# Motherboard.net
KiCad netlist of a schematic drawn in Altium Designer
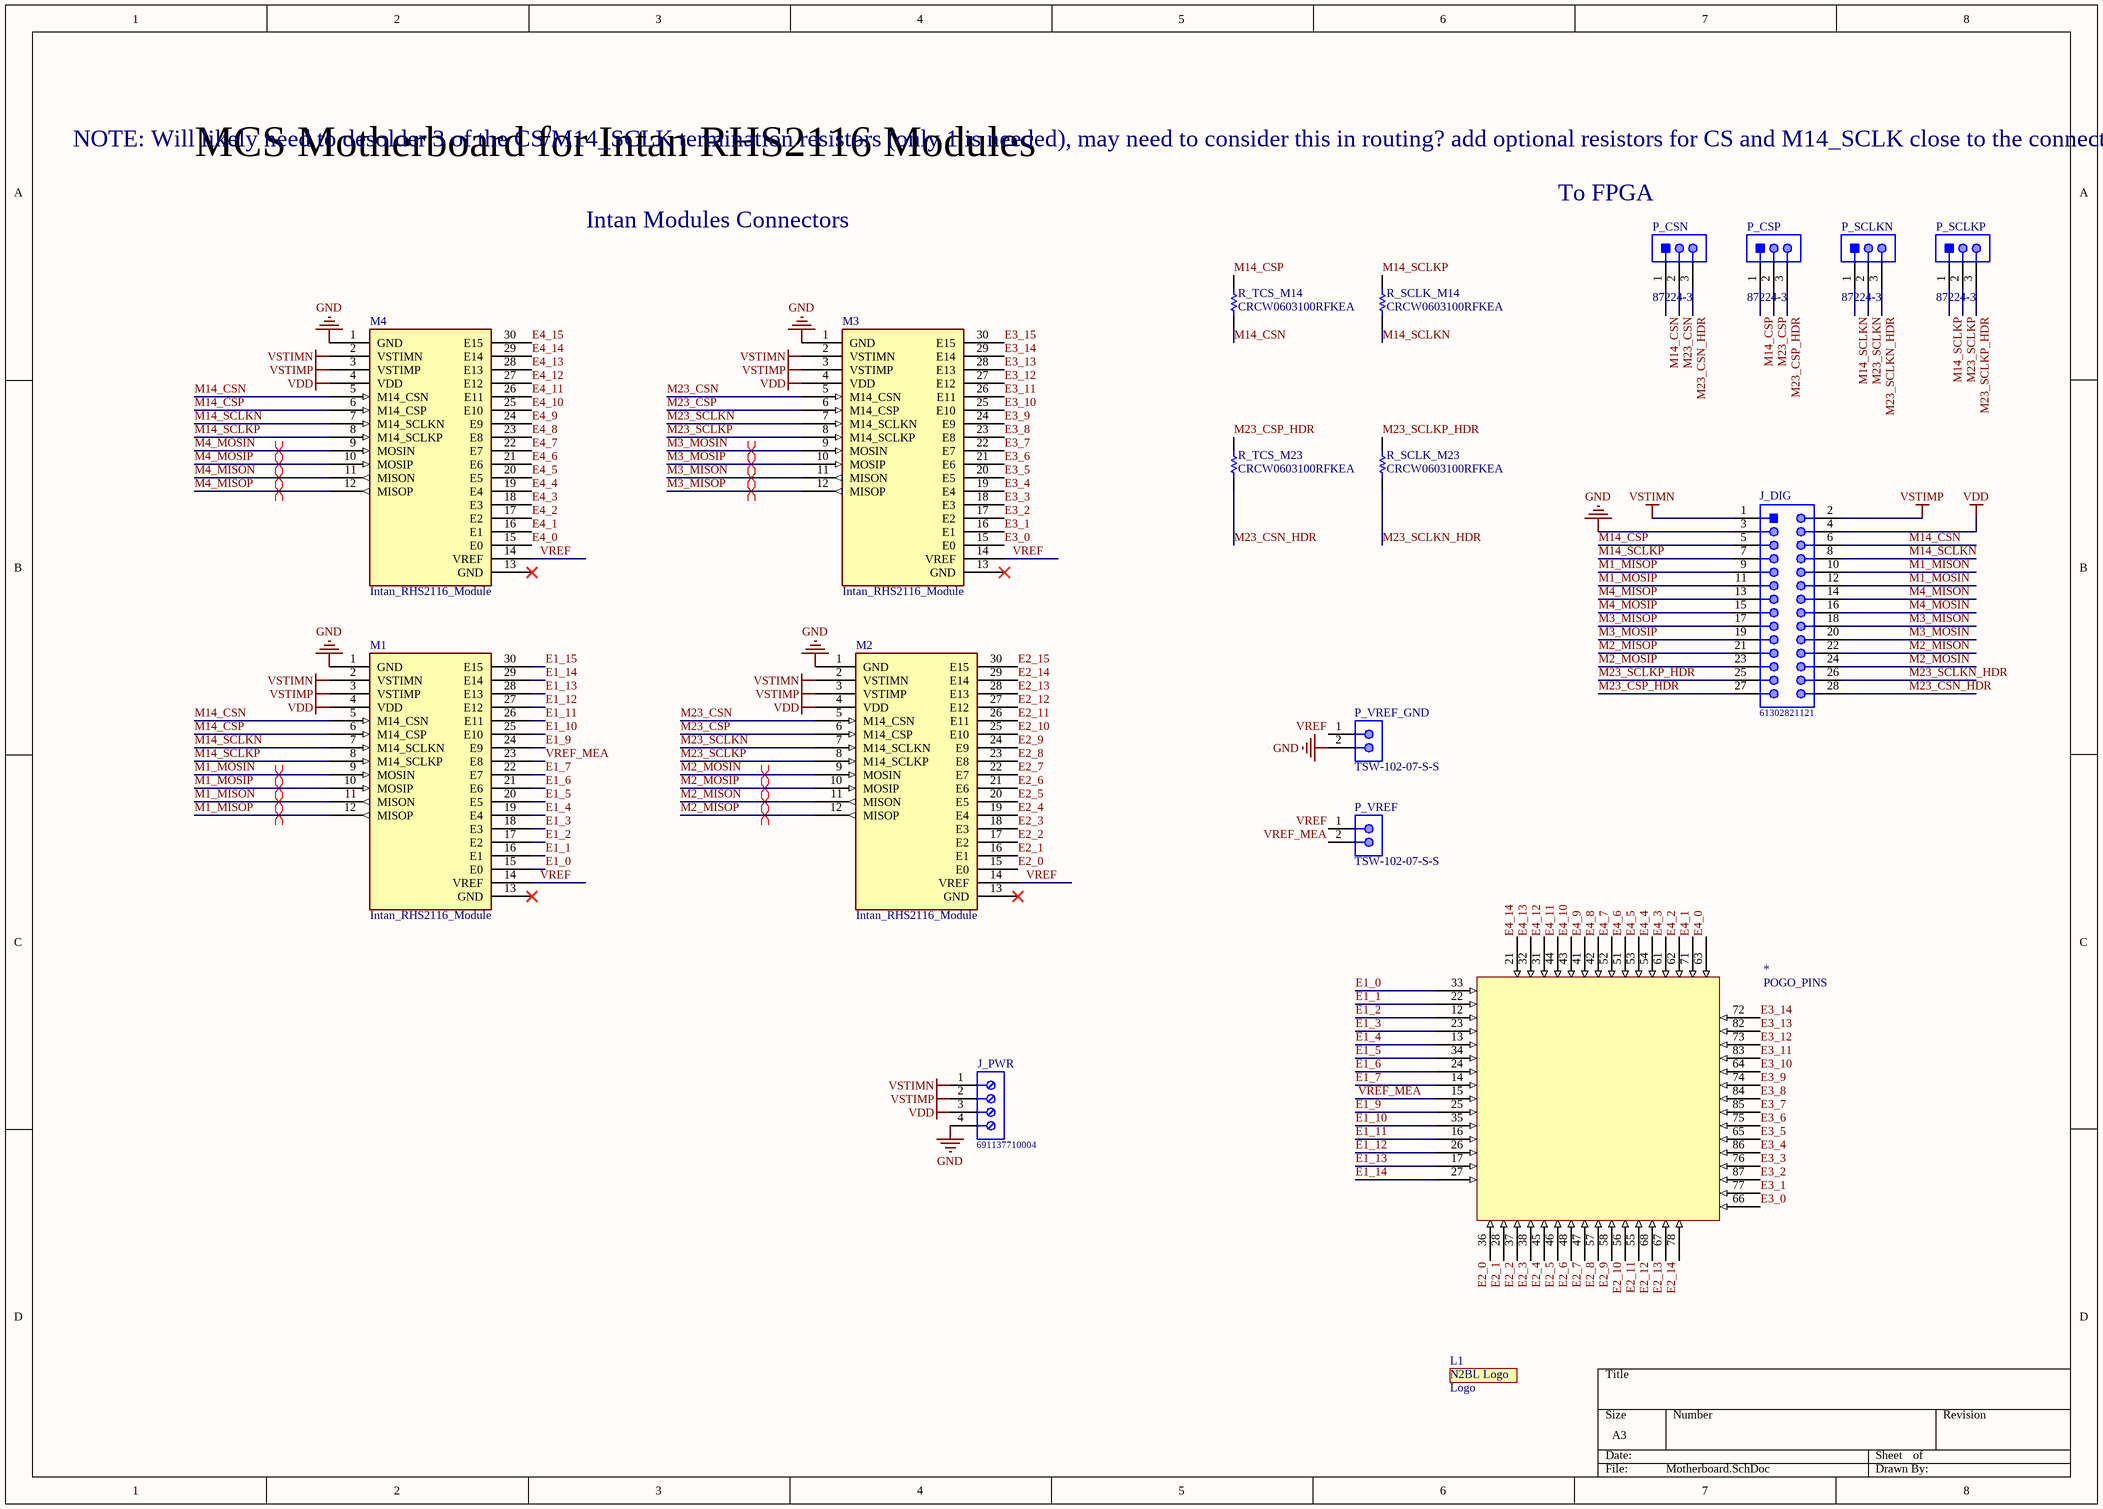
[diagram p0: Motherboard.SchDoc]

(export (version "E")
  (design (tool "Eeschema 10.0.6"))
  (components
    (comp (ref "*") (value "POGO_PINS") (footprint "POGO_PINS") (libsource (lib "V004") (part "POGO_PINS")))
    (comp (ref "J_DIG")
      (value "61302821121")
      (footprint "61302821121")
      (description "THT Vertical Pin Header WR-PHD, Pitch 2.54 mm, Dual Row, 28 pins")
      (fields (field (name "MANUFACTURER") "Wurth Elektronik") (field (name "PUBLISHER") "WurthElektronik"))
      (libsource (lib "Altium Content Vault") (part "WE-CN-2P-M-R28"))
    )
    (comp (ref "J_PWR")
      (value "691137710004")
      (footprint "691137710004")
      (description "Series 1377 - 5.00 mm Horizontal Entry with Pressure Clamp WR-TBL, 4 pin")
      (fields (field (name "MANUFACTURER") "Wurth Elektronik") (field (name "PUBLISHER") "WurthElektronik"))
      (libsource (lib "Altium Content Vault") (part "WE-CN-1P-F-TB4"))
    )
    (comp (ref "L1")
      (value "Logo")
      (footprint "N2BL_Logo")
      (libsource (lib "logo") (part "Neuron To Brain Lab Logo"))
    )
    (comp (ref "M1")
      (value "Intan_RHS2116_Module")
      (footprint "Intan_RHS2116_Module")
      (libsource (lib "V004") (part "Intan_RHS2116_Module"))
    )
    (comp (ref "M2")
      (value "Intan_RHS2116_Module")
      (footprint "Intan_RHS2116_Module")
      (libsource (lib "V004") (part "Intan_RHS2116_Module"))
    )
    (comp (ref "M3")
      (value "Intan_RHS2116_Module")
      (footprint "Intan_RHS2116_Module")
      (libsource (lib "V004") (part "Intan_RHS2116_Module"))
    )
    (comp (ref "M4")
      (value "Intan_RHS2116_Module")
      (footprint "Intan_RHS2116_Module")
      (libsource (lib "V004") (part "Intan_RHS2116_Module"))
    )
    (comp (ref "P_CSN")
      (value "87224-3")
      (footprint "TECO-87224-3_V")
      (fields (field (name "MANUFACTURER") "TE Connectivity"))
      (libsource (lib "Altium Content Vault") (part "CN-1P-M-R3"))
    )
    (comp (ref "P_CSP")
      (value "87224-3")
      (footprint "TECO-87224-3_V")
      (fields (field (name "MANUFACTURER") "TE Connectivity"))
      (libsource (lib "Altium Content Vault") (part "CN-1P-M-R3"))
    )
    (comp (ref "P_SCLKN")
      (value "87224-3")
      (footprint "TECO-87224-3_V")
      (fields (field (name "MANUFACTURER") "TE Connectivity"))
      (libsource (lib "Altium Content Vault") (part "CN-1P-M-R3"))
    )
    (comp (ref "P_SCLKP")
      (value "87224-3")
      (footprint "TECO-87224-3_V")
      (fields (field (name "MANUFACTURER") "TE Connectivity"))
      (libsource (lib "Altium Content Vault") (part "CN-1P-M-R3"))
    )
    (comp (ref "P_VREF")
      (value "TSW-102-07-S-S")
      (footprint "SMTC-TSW-102-07-S-S")
      (fields (field (name "MANUFACTURER") "Samtec"))
      (libsource (lib "Altium Content Vault") (part "CN-1P-M-R2"))
    )
    (comp (ref "P_VREF_GND")
      (value "TSW-102-07-S-S")
      (footprint "SMTC-TSW-102-07-S-S")
      (fields (field (name "MANUFACTURER") "Samtec"))
      (libsource (lib "Altium Content Vault") (part "CN-1P-M-R2"))
    )
    (comp (ref "R_SCLK_M14")
      (value "CRCW0603100RFKEA")
      (footprint "RESC1609X50X30ML8T20")
      (description "Chip Resistor, 100 Ohm, +/- 1%, 100 mW,-55 to 155 degC, 0603 (1608 Metric), RoHS, Tape and Ree")
      (fields (field (name "MANUFACTURER") "Vishay Semiconductor"))
      (libsource (lib "Altium Content Vault") (part "RES-2"))
    )
    (comp (ref "R_SCLK_M23")
      (value "CRCW0603100RFKEA")
      (footprint "RESC1609X50X30ML8T20")
      (description "Chip Resistor, 100 Ohm, +/- 1%, 100 mW,-55 to 155 degC, 0603 (1608 Metric), RoHS, Tape and Ree")
      (fields (field (name "MANUFACTURER") "Vishay Semiconductor"))
      (libsource (lib "Altium Content Vault") (part "RES-2"))
    )
    (comp (ref "R_TCS_M14")
      (value "CRCW0603100RFKEA")
      (footprint "RESC1609X50X30ML8T20")
      (description "Chip Resistor, 100 Ohm, +/- 1%, 100 mW,-55 to 155 degC, 0603 (1608 Metric), RoHS, Tape and Ree")
      (fields (field (name "MANUFACTURER") "Vishay Semiconductor"))
      (libsource (lib "Altium Content Vault") (part "RES-2"))
    )
    (comp (ref "R_TCS_M23")
      (value "CRCW0603100RFKEA")
      (footprint "RESC1609X50X30ML8T20")
      (description "Chip Resistor, 100 Ohm, +/- 1%, 100 mW,-55 to 155 degC, 0603 (1608 Metric), RoHS, Tape and Ree")
      (fields (field (name "MANUFACTURER") "Vishay Semiconductor"))
      (libsource (lib "Altium Content Vault") (part "RES-2"))
    )
  )
  (nets
    (net (code "1") (name "/E1_0") (class "Default")
      (node (ref "*") (pin "33") (pintype "input"))
      (node (ref "M1") (pin "15") (pinfunction "E0_15") (pintype "passive"))
    )
    (net (code "2") (name "/E1_1") (class "Default")
      (node (ref "*") (pin "22") (pintype "input"))
      (node (ref "M1") (pin "16") (pinfunction "E1_16") (pintype "passive"))
    )
    (net (code "3") (name "/E1_2") (class "Default")
      (node (ref "*") (pin "12") (pintype "input"))
      (node (ref "M1") (pin "17") (pinfunction "E2_17") (pintype "passive"))
    )
    (net (code "4") (name "/E1_3") (class "Default")
      (node (ref "*") (pin "23") (pintype "input"))
      (node (ref "M1") (pin "18") (pinfunction "E3_18") (pintype "passive"))
    )
    (net (code "5") (name "/E1_4") (class "Default")
      (node (ref "*") (pin "13") (pintype "input"))
      (node (ref "M1") (pin "19") (pinfunction "E4_19") (pintype "passive"))
    )
    (net (code "6") (name "/E1_5") (class "Default")
      (node (ref "*") (pin "34") (pintype "input"))
      (node (ref "M1") (pin "20") (pinfunction "E5_20") (pintype "passive"))
    )
    (net (code "7") (name "/E1_6") (class "Default")
      (node (ref "*") (pin "24") (pintype "input"))
      (node (ref "M1") (pin "21") (pinfunction "E6_21") (pintype "passive"))
    )
    (net (code "8") (name "/E1_7") (class "Default")
      (node (ref "*") (pin "14") (pintype "input"))
      (node (ref "M1") (pin "22") (pinfunction "E7_22") (pintype "passive"))
    )
    (net (code "9") (name "/E1_9") (class "Default")
      (node (ref "*") (pin "25") (pintype "input"))
      (node (ref "M1") (pin "24") (pinfunction "E9_24") (pintype "passive"))
    )
    (net (code "10") (name "/E1_10") (class "Default")
      (node (ref "*") (pin "35") (pintype "input"))
      (node (ref "M1") (pin "25") (pinfunction "E10_25") (pintype "passive"))
    )
    (net (code "11") (name "/E1_11") (class "Default")
      (node (ref "*") (pin "16") (pintype "input"))
      (node (ref "M1") (pin "26") (pinfunction "E11_26") (pintype "passive"))
    )
    (net (code "12") (name "/E1_12") (class "Default")
      (node (ref "*") (pin "26") (pintype "input"))
      (node (ref "M1") (pin "27") (pinfunction "E12_27") (pintype "passive"))
    )
    (net (code "13") (name "/E1_13") (class "Default")
      (node (ref "*") (pin "17") (pintype "input"))
      (node (ref "M1") (pin "28") (pinfunction "E13_28") (pintype "passive"))
    )
    (net (code "14") (name "/E1_14") (class "Default")
      (node (ref "*") (pin "27") (pintype "input"))
      (node (ref "M1") (pin "29") (pinfunction "E14_29") (pintype "passive"))
    )
    (net (code "15") (name "/E1_15") (class "Default")
      (node (ref "M1") (pin "30") (pinfunction "E15_30") (pintype "passive"))
    )
    (net (code "16") (name "/E2_0") (class "Default")
      (node (ref "*") (pin "36") (pintype "input"))
      (node (ref "M2") (pin "15") (pinfunction "E0_15") (pintype "passive"))
    )
    (net (code "17") (name "/E2_1") (class "Default")
      (node (ref "*") (pin "28") (pintype "input"))
      (node (ref "M2") (pin "16") (pinfunction "E1_16") (pintype "passive"))
    )
    (net (code "18") (name "/E2_2") (class "Default")
      (node (ref "*") (pin "37") (pintype "input"))
      (node (ref "M2") (pin "17") (pinfunction "E2_17") (pintype "passive"))
    )
    (net (code "19") (name "/E2_3") (class "Default")
      (node (ref "*") (pin "38") (pintype "input"))
      (node (ref "M2") (pin "18") (pinfunction "E3_18") (pintype "passive"))
    )
    (net (code "20") (name "/E2_4") (class "Default")
      (node (ref "*") (pin "45") (pintype "input"))
      (node (ref "M2") (pin "19") (pinfunction "E4_19") (pintype "passive"))
    )
    (net (code "21") (name "/E2_5") (class "Default")
      (node (ref "*") (pin "46") (pintype "input"))
      (node (ref "M2") (pin "20") (pinfunction "E5_20") (pintype "passive"))
    )
    (net (code "22") (name "/E2_6") (class "Default")
      (node (ref "*") (pin "48") (pintype "input"))
      (node (ref "M2") (pin "21") (pinfunction "E6_21") (pintype "passive"))
    )
    (net (code "23") (name "/E2_7") (class "Default")
      (node (ref "*") (pin "47") (pintype "input"))
      (node (ref "M2") (pin "22") (pinfunction "E7_22") (pintype "passive"))
    )
    (net (code "24") (name "/E2_8") (class "Default")
      (node (ref "*") (pin "57") (pintype "input"))
      (node (ref "M2") (pin "23") (pinfunction "E8_23") (pintype "passive"))
    )
    (net (code "25") (name "/E2_9") (class "Default")
      (node (ref "*") (pin "58") (pintype "input"))
      (node (ref "M2") (pin "24") (pinfunction "E9_24") (pintype "passive"))
    )
    (net (code "26") (name "/E2_10") (class "Default")
      (node (ref "*") (pin "56") (pintype "input"))
      (node (ref "M2") (pin "25") (pinfunction "E10_25") (pintype "passive"))
    )
    (net (code "27") (name "/E2_11") (class "Default")
      (node (ref "*") (pin "55") (pintype "input"))
      (node (ref "M2") (pin "26") (pinfunction "E11_26") (pintype "passive"))
    )
    (net (code "28") (name "/E2_12") (class "Default")
      (node (ref "*") (pin "68") (pintype "input"))
      (node (ref "M2") (pin "27") (pinfunction "E12_27") (pintype "passive"))
    )
    (net (code "29") (name "/E2_13") (class "Default")
      (node (ref "*") (pin "67") (pintype "input"))
      (node (ref "M2") (pin "28") (pinfunction "E13_28") (pintype "passive"))
    )
    (net (code "30") (name "/E2_14") (class "Default")
      (node (ref "*") (pin "78") (pintype "input"))
      (node (ref "M2") (pin "29") (pinfunction "E14_29") (pintype "passive"))
    )
    (net (code "31") (name "/E2_15") (class "Default")
      (node (ref "M2") (pin "30") (pinfunction "E15_30") (pintype "passive"))
    )
    (net (code "32") (name "/E3_0") (class "Default")
      (node (ref "*") (pin "66") (pintype "input"))
      (node (ref "M3") (pin "15") (pinfunction "E0_15") (pintype "passive"))
    )
    (net (code "33") (name "/E3_1") (class "Default")
      (node (ref "*") (pin "77") (pintype "input"))
      (node (ref "M3") (pin "16") (pinfunction "E1_16") (pintype "passive"))
    )
    (net (code "34") (name "/E3_2") (class "Default")
      (node (ref "*") (pin "87") (pintype "input"))
      (node (ref "M3") (pin "17") (pinfunction "E2_17") (pintype "passive"))
    )
    (net (code "35") (name "/E3_3") (class "Default")
      (node (ref "*") (pin "76") (pintype "input"))
      (node (ref "M3") (pin "18") (pinfunction "E3_18") (pintype "passive"))
    )
    (net (code "36") (name "/E3_4") (class "Default")
      (node (ref "*") (pin "86") (pintype "input"))
      (node (ref "M3") (pin "19") (pinfunction "E4_19") (pintype "passive"))
    )
    (net (code "37") (name "/E3_5") (class "Default")
      (node (ref "*") (pin "65") (pintype "input"))
      (node (ref "M3") (pin "20") (pinfunction "E5_20") (pintype "passive"))
    )
    (net (code "38") (name "/E3_6") (class "Default")
      (node (ref "*") (pin "75") (pintype "input"))
      (node (ref "M3") (pin "21") (pinfunction "E6_21") (pintype "passive"))
    )
    (net (code "39") (name "/E3_7") (class "Default")
      (node (ref "*") (pin "85") (pintype "input"))
      (node (ref "M3") (pin "22") (pinfunction "E7_22") (pintype "passive"))
    )
    (net (code "40") (name "/E3_8") (class "Default")
      (node (ref "*") (pin "84") (pintype "input"))
      (node (ref "M3") (pin "23") (pinfunction "E8_23") (pintype "passive"))
    )
    (net (code "41") (name "/E3_9") (class "Default")
      (node (ref "*") (pin "74") (pintype "input"))
      (node (ref "M3") (pin "24") (pinfunction "E9_24") (pintype "passive"))
    )
    (net (code "42") (name "/E3_10") (class "Default")
      (node (ref "*") (pin "64") (pintype "input"))
      (node (ref "M3") (pin "25") (pinfunction "E10_25") (pintype "passive"))
    )
    (net (code "43") (name "/E3_11") (class "Default")
      (node (ref "*") (pin "83") (pintype "input"))
      (node (ref "M3") (pin "26") (pinfunction "E11_26") (pintype "passive"))
    )
    (net (code "44") (name "/E3_12") (class "Default")
      (node (ref "*") (pin "73") (pintype "input"))
      (node (ref "M3") (pin "27") (pinfunction "E12_27") (pintype "passive"))
    )
    (net (code "45") (name "/E3_13") (class "Default")
      (node (ref "*") (pin "82") (pintype "input"))
      (node (ref "M3") (pin "28") (pinfunction "E13_28") (pintype "passive"))
    )
    (net (code "46") (name "/E3_14") (class "Default")
      (node (ref "*") (pin "72") (pintype "input"))
      (node (ref "M3") (pin "29") (pinfunction "E14_29") (pintype "passive"))
    )
    (net (code "47") (name "/E3_15") (class "Default")
      (node (ref "M3") (pin "30") (pinfunction "E15_30") (pintype "passive"))
    )
    (net (code "48") (name "/E4_0") (class "Default")
      (node (ref "*") (pin "63") (pintype "input"))
      (node (ref "M4") (pin "15") (pinfunction "E0_15") (pintype "passive"))
    )
    (net (code "49") (name "/E4_1") (class "Default")
      (node (ref "*") (pin "71") (pintype "input"))
      (node (ref "M4") (pin "16") (pinfunction "E1_16") (pintype "passive"))
    )
    (net (code "50") (name "/E4_2") (class "Default")
      (node (ref "*") (pin "62") (pintype "input"))
      (node (ref "M4") (pin "17") (pinfunction "E2_17") (pintype "passive"))
    )
    (net (code "51") (name "/E4_3") (class "Default")
      (node (ref "*") (pin "61") (pintype "input"))
      (node (ref "M4") (pin "18") (pinfunction "E3_18") (pintype "passive"))
    )
    (net (code "52") (name "/E4_4") (class "Default")
      (node (ref "*") (pin "54") (pintype "input"))
      (node (ref "M4") (pin "19") (pinfunction "E4_19") (pintype "passive"))
    )
    (net (code "53") (name "/E4_5") (class "Default")
      (node (ref "*") (pin "53") (pintype "input"))
      (node (ref "M4") (pin "20") (pinfunction "E5_20") (pintype "passive"))
    )
    (net (code "54") (name "/E4_6") (class "Default")
      (node (ref "*") (pin "51") (pintype "input"))
      (node (ref "M4") (pin "21") (pinfunction "E6_21") (pintype "passive"))
    )
    (net (code "55") (name "/E4_7") (class "Default")
      (node (ref "*") (pin "52") (pintype "input"))
      (node (ref "M4") (pin "22") (pinfunction "E7_22") (pintype "passive"))
    )
    (net (code "56") (name "/E4_8") (class "Default")
      (node (ref "*") (pin "42") (pintype "input"))
      (node (ref "M4") (pin "23") (pinfunction "E8_23") (pintype "passive"))
    )
    (net (code "57") (name "/E4_9") (class "Default")
      (node (ref "*") (pin "41") (pintype "input"))
      (node (ref "M4") (pin "24") (pinfunction "E9_24") (pintype "passive"))
    )
    (net (code "58") (name "/E4_10") (class "Default")
      (node (ref "*") (pin "43") (pintype "input"))
      (node (ref "M4") (pin "25") (pinfunction "E10_25") (pintype "passive"))
    )
    (net (code "59") (name "/E4_11") (class "Default")
      (node (ref "*") (pin "44") (pintype "input"))
      (node (ref "M4") (pin "26") (pinfunction "E11_26") (pintype "passive"))
    )
    (net (code "60") (name "/E4_12") (class "Default")
      (node (ref "*") (pin "31") (pintype "input"))
      (node (ref "M4") (pin "27") (pinfunction "E12_27") (pintype "passive"))
    )
    (net (code "61") (name "/E4_13") (class "Default")
      (node (ref "*") (pin "32") (pintype "input"))
      (node (ref "M4") (pin "28") (pinfunction "E13_28") (pintype "passive"))
    )
    (net (code "62") (name "/E4_14") (class "Default")
      (node (ref "*") (pin "21") (pintype "input"))
      (node (ref "M4") (pin "29") (pinfunction "E14_29") (pintype "passive"))
    )
    (net (code "63") (name "/E4_15") (class "Default")
      (node (ref "M4") (pin "30") (pinfunction "E15_30") (pintype "passive"))
    )
    (net (code "64") (name "/M1_MISON") (class "Default")
      (node (ref "J_DIG") (pin "10") (pinfunction "10_10") (pintype "passive"))
      (node (ref "M1") (pin "11") (pinfunction "MISON_11") (pintype "output"))
    )
    (net (code "65") (name "/M1_MISOP") (class "Default")
      (node (ref "J_DIG") (pin "9") (pinfunction "9_9") (pintype "passive"))
      (node (ref "M1") (pin "12") (pinfunction "MISOP_12") (pintype "output"))
    )
    (net (code "66") (name "/M1_MOSIN") (class "Default")
      (node (ref "J_DIG") (pin "12") (pinfunction "12_12") (pintype "passive"))
      (node (ref "M1") (pin "9") (pinfunction "MOSIN_9") (pintype "input"))
    )
    (net (code "67") (name "/M1_MOSIP") (class "Default")
      (node (ref "J_DIG") (pin "11") (pinfunction "11_11") (pintype "passive"))
      (node (ref "M1") (pin "10") (pinfunction "MOSIP_10") (pintype "input"))
    )
    (net (code "68") (name "/M2_MISON") (class "Default")
      (node (ref "J_DIG") (pin "22") (pinfunction "22_22") (pintype "passive"))
      (node (ref "M2") (pin "11") (pinfunction "MISON_11") (pintype "output"))
    )
    (net (code "69") (name "/M2_MISOP") (class "Default")
      (node (ref "J_DIG") (pin "21") (pinfunction "21_21") (pintype "passive"))
      (node (ref "M2") (pin "12") (pinfunction "MISOP_12") (pintype "output"))
    )
    (net (code "70") (name "/M2_MOSIN") (class "Default")
      (node (ref "J_DIG") (pin "24") (pinfunction "24_24") (pintype "passive"))
      (node (ref "M2") (pin "9") (pinfunction "MOSIN_9") (pintype "input"))
    )
    (net (code "71") (name "/M2_MOSIP") (class "Default")
      (node (ref "J_DIG") (pin "23") (pinfunction "23_23") (pintype "passive"))
      (node (ref "M2") (pin "10") (pinfunction "MOSIP_10") (pintype "input"))
    )
    (net (code "72") (name "/M3_MISON") (class "Default")
      (node (ref "J_DIG") (pin "18") (pinfunction "18_18") (pintype "passive"))
      (node (ref "M3") (pin "11") (pinfunction "MISON_11") (pintype "output"))
    )
    (net (code "73") (name "/M3_MISOP") (class "Default")
      (node (ref "J_DIG") (pin "17") (pinfunction "17_17") (pintype "passive"))
      (node (ref "M3") (pin "12") (pinfunction "MISOP_12") (pintype "output"))
    )
    (net (code "74") (name "/M3_MOSIN") (class "Default")
      (node (ref "J_DIG") (pin "20") (pinfunction "20_20") (pintype "passive"))
      (node (ref "M3") (pin "9") (pinfunction "MOSIN_9") (pintype "input"))
    )
    (net (code "75") (name "/M3_MOSIP") (class "Default")
      (node (ref "J_DIG") (pin "19") (pinfunction "19_19") (pintype "passive"))
      (node (ref "M3") (pin "10") (pinfunction "MOSIP_10") (pintype "input"))
    )
    (net (code "76") (name "/M4_MISON") (class "Default")
      (node (ref "J_DIG") (pin "14") (pinfunction "14_14") (pintype "passive"))
      (node (ref "M4") (pin "11") (pinfunction "MISON_11") (pintype "output"))
    )
    (net (code "77") (name "/M4_MISOP") (class "Default")
      (node (ref "J_DIG") (pin "13") (pinfunction "13_13") (pintype "passive"))
      (node (ref "M4") (pin "12") (pinfunction "MISOP_12") (pintype "output"))
    )
    (net (code "78") (name "/M4_MOSIN") (class "Default")
      (node (ref "J_DIG") (pin "16") (pinfunction "16_16") (pintype "passive"))
      (node (ref "M4") (pin "9") (pinfunction "MOSIN_9") (pintype "input"))
    )
    (net (code "79") (name "/M4_MOSIP") (class "Default")
      (node (ref "J_DIG") (pin "15") (pinfunction "15_15") (pintype "passive"))
      (node (ref "M4") (pin "10") (pinfunction "MOSIP_10") (pintype "input"))
    )
    (net (code "80") (name "/M14_CSN") (class "Default")
      (node (ref "J_DIG") (pin "6") (pinfunction "6_6") (pintype "passive"))
      (node (ref "M1") (pin "5") (pinfunction "M14_CSN_5") (pintype "input"))
      (node (ref "M4") (pin "5") (pinfunction "M14_CSN_5") (pintype "input"))
      (node (ref "P_CSN") (pin "1") (pinfunction "1_1") (pintype "passive"))
      (node (ref "R_TCS_M14") (pin "1") (pinfunction "1_1") (pintype "passive"))
    )
    (net (code "81") (name "/M14_CSP") (class "Default")
      (node (ref "J_DIG") (pin "5") (pinfunction "5_5") (pintype "passive"))
      (node (ref "M1") (pin "6") (pinfunction "M14_CSP_6") (pintype "input"))
      (node (ref "M4") (pin "6") (pinfunction "M14_CSP_6") (pintype "input"))
      (node (ref "P_CSP") (pin "1") (pinfunction "1_1") (pintype "passive"))
      (node (ref "R_TCS_M14") (pin "2") (pinfunction "2_2") (pintype "passive"))
    )
    (net (code "82") (name "/M14_SCLKN") (class "Default")
      (node (ref "J_DIG") (pin "8") (pinfunction "8_8") (pintype "passive"))
      (node (ref "M1") (pin "7") (pinfunction "M14_SCLKN_7") (pintype "input"))
      (node (ref "M4") (pin "7") (pinfunction "M14_SCLKN_7") (pintype "input"))
      (node (ref "P_SCLKN") (pin "1") (pinfunction "1_1") (pintype "passive"))
      (node (ref "R_SCLK_M14") (pin "1") (pinfunction "1_1") (pintype "passive"))
    )
    (net (code "83") (name "/M14_SCLKP") (class "Default")
      (node (ref "J_DIG") (pin "7") (pinfunction "7_7") (pintype "passive"))
      (node (ref "M1") (pin "8") (pinfunction "M14_SCLKP_8") (pintype "input"))
      (node (ref "M4") (pin "8") (pinfunction "M14_SCLKP_8") (pintype "input"))
      (node (ref "P_SCLKP") (pin "1") (pinfunction "1_1") (pintype "passive"))
      (node (ref "R_SCLK_M14") (pin "2") (pinfunction "2_2") (pintype "passive"))
    )
    (net (code "84") (name "/M23_CSN") (class "Default")
      (node (ref "M2") (pin "5") (pinfunction "M14_CSN_5") (pintype "input"))
      (node (ref "M3") (pin "5") (pinfunction "M14_CSN_5") (pintype "input"))
      (node (ref "P_CSN") (pin "2") (pinfunction "2_2") (pintype "passive"))
    )
    (net (code "85") (name "/M23_CSN_HDR") (class "Default")
      (node (ref "J_DIG") (pin "28") (pinfunction "28_28") (pintype "passive"))
      (node (ref "P_CSN") (pin "3") (pinfunction "3_3") (pintype "passive"))
      (node (ref "R_TCS_M23") (pin "1") (pinfunction "1_1") (pintype "passive"))
    )
    (net (code "86") (name "/M23_CSP") (class "Default")
      (node (ref "M2") (pin "6") (pinfunction "M14_CSP_6") (pintype "input"))
      (node (ref "M3") (pin "6") (pinfunction "M14_CSP_6") (pintype "input"))
      (node (ref "P_CSP") (pin "2") (pinfunction "2_2") (pintype "passive"))
    )
    (net (code "87") (name "/M23_CSP_HDR") (class "Default")
      (node (ref "J_DIG") (pin "27") (pinfunction "27_27") (pintype "passive"))
      (node (ref "P_CSP") (pin "3") (pinfunction "3_3") (pintype "passive"))
      (node (ref "R_TCS_M23") (pin "2") (pinfunction "2_2") (pintype "passive"))
    )
    (net (code "88") (name "/M23_SCLKN") (class "Default")
      (node (ref "M2") (pin "7") (pinfunction "M14_SCLKN_7") (pintype "input"))
      (node (ref "M3") (pin "7") (pinfunction "M14_SCLKN_7") (pintype "input"))
      (node (ref "P_SCLKN") (pin "2") (pinfunction "2_2") (pintype "passive"))
    )
    (net (code "89") (name "/M23_SCLKN_HDR") (class "Default")
      (node (ref "J_DIG") (pin "26") (pinfunction "26_26") (pintype "passive"))
      (node (ref "P_SCLKN") (pin "3") (pinfunction "3_3") (pintype "passive"))
      (node (ref "R_SCLK_M23") (pin "1") (pinfunction "1_1") (pintype "passive"))
    )
    (net (code "90") (name "/M23_SCLKP") (class "Default")
      (node (ref "M2") (pin "8") (pinfunction "M14_SCLKP_8") (pintype "input"))
      (node (ref "M3") (pin "8") (pinfunction "M14_SCLKP_8") (pintype "input"))
      (node (ref "P_SCLKP") (pin "2") (pinfunction "2_2") (pintype "passive"))
    )
    (net (code "91") (name "/M23_SCLKP_HDR") (class "Default")
      (node (ref "J_DIG") (pin "25") (pinfunction "25_25") (pintype "passive"))
      (node (ref "P_SCLKP") (pin "3") (pinfunction "3_3") (pintype "passive"))
      (node (ref "R_SCLK_M23") (pin "2") (pinfunction "2_2") (pintype "passive"))
    )
    (net (code "92") (name "/VREF") (class "Default")
      (node (ref "M1") (pin "14") (pinfunction "VREF_14") (pintype "passive"))
      (node (ref "M2") (pin "14") (pinfunction "VREF_14") (pintype "passive"))
      (node (ref "M3") (pin "14") (pinfunction "VREF_14") (pintype "passive"))
      (node (ref "M4") (pin "14") (pinfunction "VREF_14") (pintype "passive"))
      (node (ref "P_VREF") (pin "1") (pinfunction "1_1") (pintype "passive"))
      (node (ref "P_VREF_GND") (pin "1") (pinfunction "1_1") (pintype "passive"))
    )
    (net (code "93") (name "/VREF_MEA") (class "Default")
      (node (ref "*") (pin "15") (pintype "input"))
      (node (ref "M1") (pin "23") (pinfunction "E8_23") (pintype "passive"))
      (node (ref "P_VREF") (pin "2") (pinfunction "2_2") (pintype "passive"))
    )
    (net (code "94") (name "GND") (class "Default")
      (node (ref "J_DIG") (pin "3") (pinfunction "3_3") (pintype "passive"))
      (node (ref "J_PWR") (pin "4") (pinfunction "4_4") (pintype "passive"))
      (node (ref "M1") (pin "1") (pinfunction "GND_1") (pintype "power_in"))
      (node (ref "M2") (pin "1") (pinfunction "GND_1") (pintype "power_in"))
      (node (ref "M3") (pin "1") (pinfunction "GND_1") (pintype "power_in"))
      (node (ref "M4") (pin "1") (pinfunction "GND_1") (pintype "power_in"))
      (node (ref "P_VREF_GND") (pin "2") (pinfunction "2_2") (pintype "passive"))
    )
    (net (code "95") (name "VDD") (class "Default")
      (node (ref "J_DIG") (pin "4") (pinfunction "4_4") (pintype "passive"))
      (node (ref "J_PWR") (pin "3") (pinfunction "3_3") (pintype "passive"))
      (node (ref "M1") (pin "4") (pinfunction "VDD_4") (pintype "power_in"))
      (node (ref "M2") (pin "4") (pinfunction "VDD_4") (pintype "power_in"))
      (node (ref "M3") (pin "4") (pinfunction "VDD_4") (pintype "power_in"))
      (node (ref "M4") (pin "4") (pinfunction "VDD_4") (pintype "power_in"))
    )
    (net (code "96") (name "VSTIMN") (class "Default")
      (node (ref "J_DIG") (pin "1") (pinfunction "1_1") (pintype "passive"))
      (node (ref "J_PWR") (pin "1") (pinfunction "1_1") (pintype "passive"))
      (node (ref "M1") (pin "2") (pinfunction "VSTIMN_2") (pintype "power_in"))
      (node (ref "M2") (pin "2") (pinfunction "VSTIMN_2") (pintype "power_in"))
      (node (ref "M3") (pin "2") (pinfunction "VSTIMN_2") (pintype "power_in"))
      (node (ref "M4") (pin "2") (pinfunction "VSTIMN_2") (pintype "power_in"))
    )
    (net (code "97") (name "VSTIMP") (class "Default")
      (node (ref "J_DIG") (pin "2") (pinfunction "2_2") (pintype "passive"))
      (node (ref "J_PWR") (pin "2") (pinfunction "2_2") (pintype "passive"))
      (node (ref "M1") (pin "3") (pinfunction "VSTIMP_3") (pintype "power_in"))
      (node (ref "M2") (pin "3") (pinfunction "VSTIMP_3") (pintype "power_in"))
      (node (ref "M3") (pin "3") (pinfunction "VSTIMP_3") (pintype "power_in"))
      (node (ref "M4") (pin "3") (pinfunction "VSTIMP_3") (pintype "power_in"))
    )
    (net (code "98") (name "unconnected-(M1-GND-Pad13)") (class "Default")
      (node (ref "M1") (pin "13") (pinfunction "GND_13") (pintype "power_in+no_connect"))
    )
    (net (code "99") (name "unconnected-(M2-GND-Pad13)") (class "Default")
      (node (ref "M2") (pin "13") (pinfunction "GND_13") (pintype "power_in+no_connect"))
    )
    (net (code "100") (name "unconnected-(M3-GND-Pad13)") (class "Default")
      (node (ref "M3") (pin "13") (pinfunction "GND_13") (pintype "power_in+no_connect"))
    )
    (net (code "101") (name "unconnected-(M4-GND-Pad13)") (class "Default")
      (node (ref "M4") (pin "13") (pinfunction "GND_13") (pintype "power_in+no_connect"))
    )
  )
)
